# Page09_WIFI_Bluetooth.net
KiCad netlist of a schematic drawn in Altium Designer
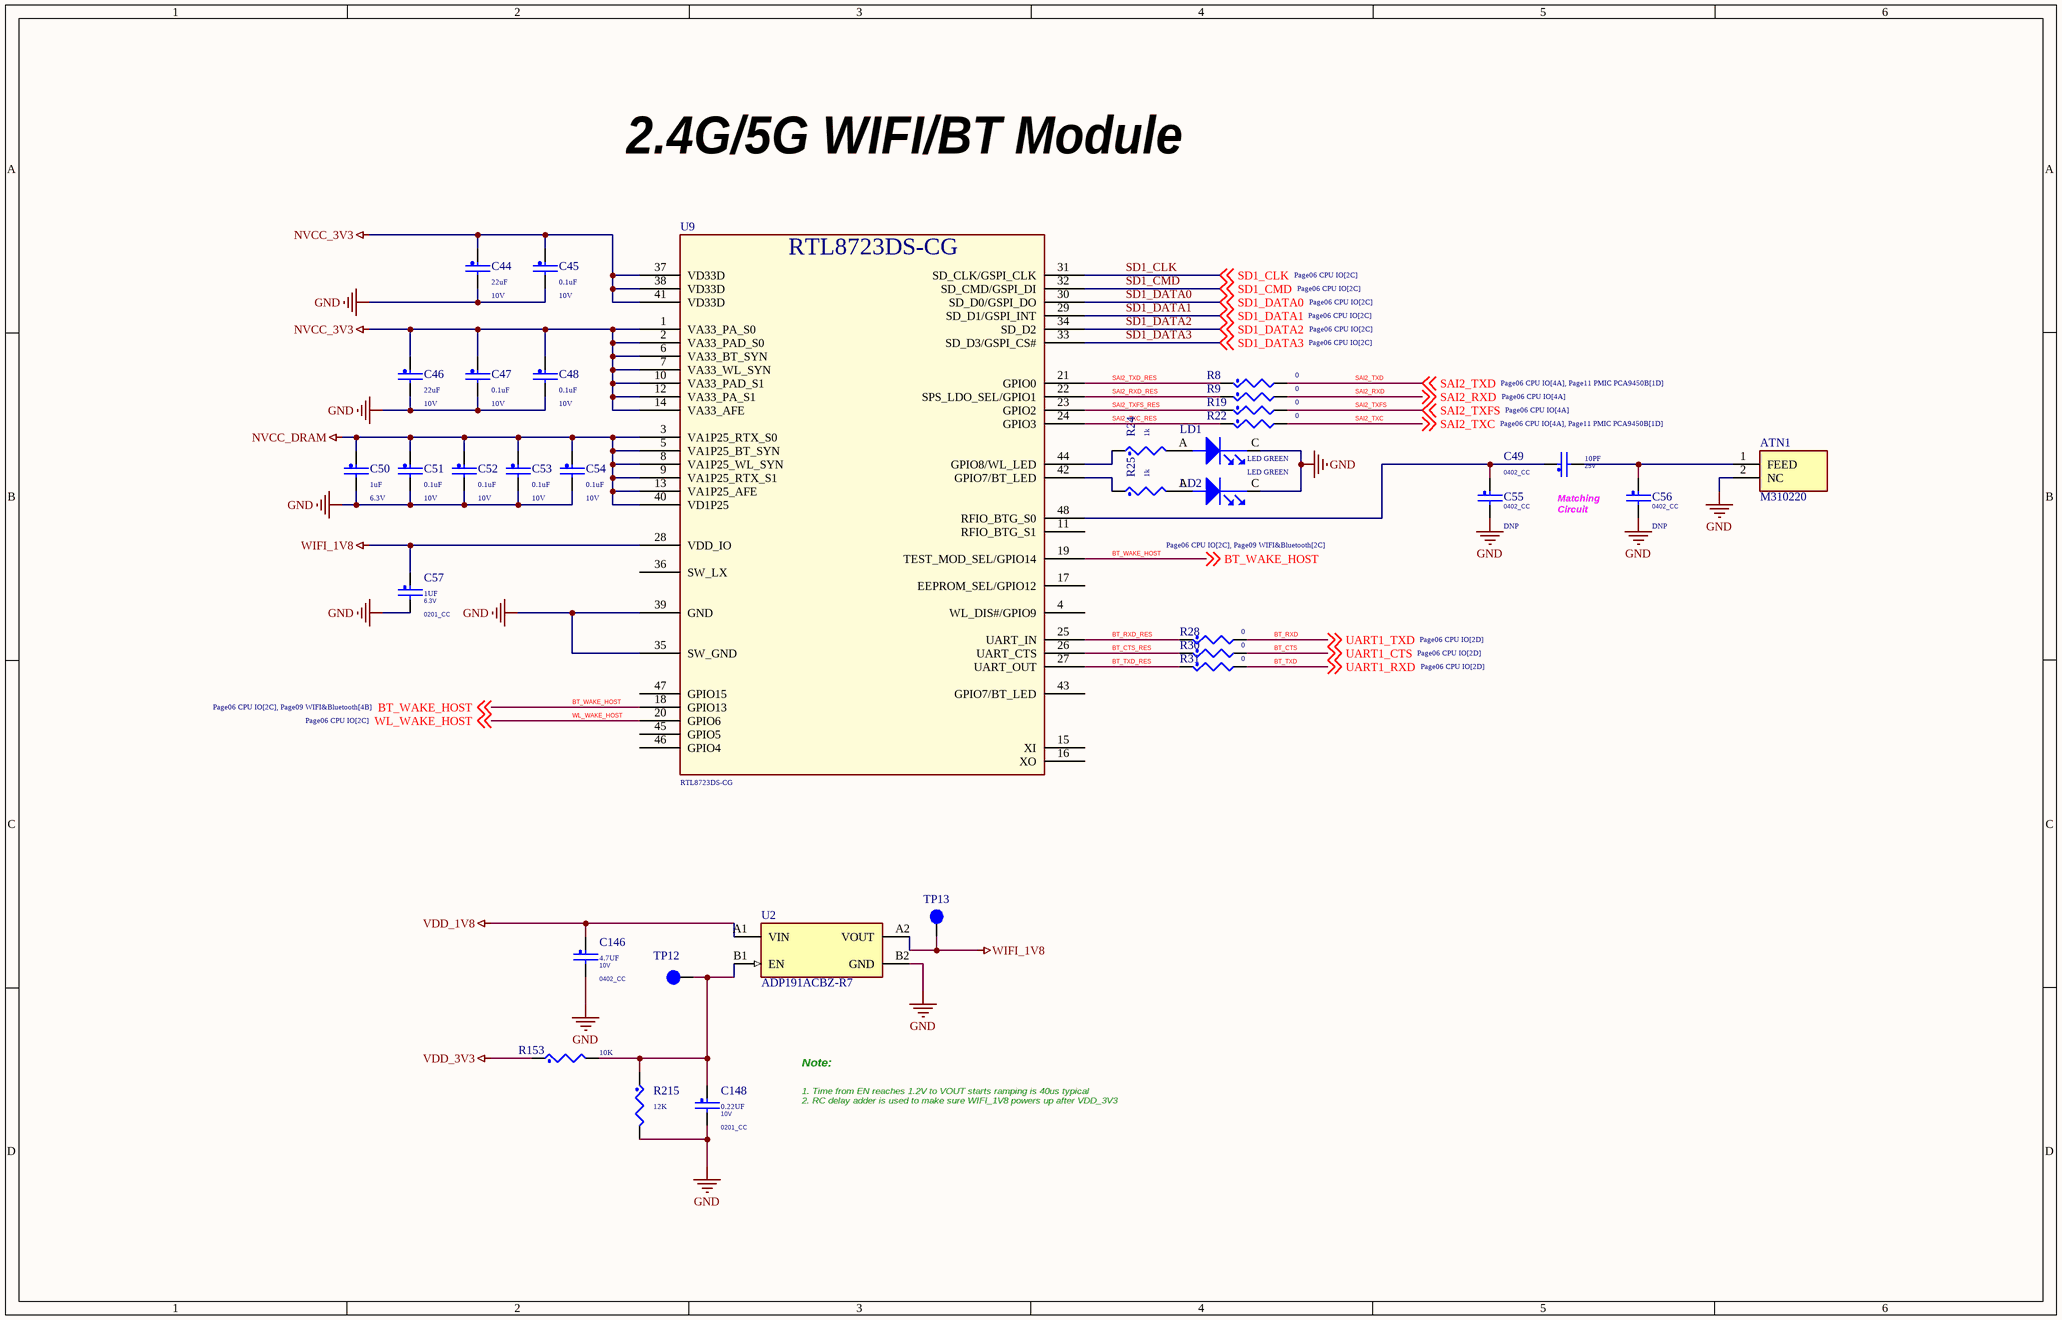
[diagram p0: Page09 WIFI&Bluetooth.SchDoc]

(export (version "E")
  (design (tool "Eeschema 10.0.6"))
  (components
    (comp (ref "ATN1")
      (value "M310220")
      (footprint "M310220")
      (description "Antennas Ceramic Chip ANTENNA BT/WLAN 2.4-2.5GHz")
      (libsource (lib "M310220") (part "M310220"))
    )
    (comp (ref "C44")
      (value "22uF")
      (footprint "0603_CC")
      (fields (field (name "VOLTAGE") "10V"))
      (libsource (lib "AA_iMX8_M_") (part "CAP_NP"))
    )
    (comp (ref "C45")
      (value "0.1uF")
      (footprint "0201_CC - C")
      (fields (field (name "VOLTAGE") "10V"))
      (libsource (lib "AA_iMX8_M_") (part "CAP_NP"))
    )
    (comp (ref "C46")
      (value "22uF")
      (footprint "0603_CC")
      (fields (field (name "VOLTAGE") "10V"))
      (libsource (lib "AA_iMX8_M_") (part "CAP_NP"))
    )
    (comp (ref "C47")
      (value "0.1uF")
      (footprint "0201_CC - C")
      (fields (field (name "VOLTAGE") "10V"))
      (libsource (lib "AA_iMX8_M_") (part "CAP_NP"))
    )
    (comp (ref "C48")
      (value "0.1uF")
      (footprint "0201_CC - C")
      (fields (field (name "VOLTAGE") "10V"))
      (libsource (lib "AA_iMX8_M_") (part "CAP_NP"))
    )
    (comp (ref "C49")
      (value "10PF")
      (footprint "0402_CC - C")
      (description "CAP CER 10PF 25V 5% C0G 0402")
      (fields
        (field (name "VOLTAGE") "25V")
        (field (name "TOLERANCE") "5%")
        (field (name "PCB FOOTPRINT") "0402_CC")
      )
      (libsource (lib "*") (part "CAP_NP"))
    )
    (comp (ref "C50")
      (value "1uF")
      (footprint "0201_CC - C")
      (fields (field (name "VOLTAGE") "6.3V"))
      (libsource (lib "AA_iMX8_M_") (part "CAP_NP"))
    )
    (comp (ref "C51")
      (value "0.1uF")
      (footprint "0201_CC - C")
      (fields (field (name "VOLTAGE") "10V"))
      (libsource (lib "AA_iMX8_M_") (part "CAP_NP"))
    )
    (comp (ref "C52")
      (value "0.1uF")
      (footprint "0201_CC - C")
      (fields (field (name "VOLTAGE") "10V"))
      (libsource (lib "AA_iMX8_M_") (part "CAP_NP"))
    )
    (comp (ref "C53")
      (value "0.1uF")
      (footprint "0201_CC - C")
      (fields (field (name "VOLTAGE") "10V"))
      (libsource (lib "AA_iMX8_M_") (part "CAP_NP"))
    )
    (comp (ref "C54")
      (value "0.1uF")
      (footprint "0201_CC - C")
      (fields (field (name "VOLTAGE") "10V"))
      (libsource (lib "AA_iMX8_M_") (part "CAP_NP"))
    )
    (comp (ref "C55")
      (value "10PF")
      (footprint "0402_CC - C")
      (description "CAP CER 10PF 25V 5% C0G 0402")
      (fields
        (field (name "ASSY_OPT") "DNP")
        (field (name "TOLERANCE") "5%")
        (field (name "VOLTAGE") "25V")
        (field (name "PCB FOOTPRINT") "0402_CC")
      )
      (libsource (lib "*") (part "CAP_NP"))
    )
    (comp (ref "C56")
      (value "10PF")
      (footprint "0402_CC - C")
      (description "CAP CER 10PF 25V 5% C0G 0402")
      (fields
        (field (name "ASSY_OPT") "DNP")
        (field (name "VOLTAGE") "25V")
        (field (name "TOLERANCE") "5%")
        (field (name "PCB FOOTPRINT") "0402_CC")
      )
      (libsource (lib "*") (part "CAP_NP"))
    )
    (comp (ref "C57")
      (value "1UF")
      (footprint "0201_CC - C")
      (description "CAP CER 1uF 6.3V 20% X5R 0201")
      (fields
        (field (name "PCB FOOTPRINT") "0201_CC")
        (field (name "TOLERANCE") "20%")
        (field (name "VOLTAGE") "6.3V")
      )
      (libsource (lib "*") (part "CAP_NP"))
    )
    (comp (ref "C146")
      (value "4.7UF")
      (footprint "0402_CC - C")
      (description "CAP CER 4.7uF 10V 10% X5R 0402")
      (fields
        (field (name "PCB FOOTPRINT") "0402_CC")
        (field (name "TOLERANCE") "10%")
        (field (name "VOLTAGE") "10V")
      )
      (libsource (lib "*") (part "CAP_NP"))
    )
    (comp (ref "C148")
      (value "0.22UF")
      (footprint "0201_CC - C")
      (description "CAP CER 0.22UF 10V 20% X5R 0201")
      (fields
        (field (name "VOLTAGE") "10V")
        (field (name "TOLERANCE") "20%")
        (field (name "PCB FOOTPRINT") "0201_CC")
      )
      (libsource (lib "*") (part "CAP_NP"))
    )
    (comp (ref "LD1")
      (value "LED GREEN")
      (footprint "LED_0603")
      (description "LED GRN SGL 25MA SMT 0603")
      (fields (field (name "VOLTAGE") "2V"))
      (libsource (lib "*") (part "LED"))
    )
    (comp (ref "LD2")
      (value "LED GREEN")
      (footprint "LED_0603")
      (description "LED GRN SGL 25MA SMT 0603")
      (fields (field (name "VOLTAGE") "2V"))
      (libsource (lib "*") (part "LED"))
    )
    (comp (ref "R8")
      (value "0")
      (footprint "0402_CC_RES")
      (description "RES MF ZERO OHM 1/16W 5% 0402")
      (fields (field (name "VOLTAGE") "1/16W") (field (name "TOLERANCE") "5%"))
      (libsource (lib "*") (part "RES"))
    )
    (comp (ref "R9")
      (value "0")
      (footprint "0402_CC_RES")
      (description "RES MF ZERO OHM 1/16W 5% 0402")
      (fields (field (name "VOLTAGE") "1/16W") (field (name "TOLERANCE") "5%"))
      (libsource (lib "*") (part "RES"))
    )
    (comp (ref "R19")
      (value "0")
      (footprint "0402_CC_RES")
      (description "RES MF ZERO OHM 1/16W 5% 0402")
      (fields (field (name "VOLTAGE") "1/16W") (field (name "TOLERANCE") "5%"))
      (libsource (lib "*") (part "RES"))
    )
    (comp (ref "R22")
      (value "0")
      (footprint "0402_CC_RES")
      (description "RES MF ZERO OHM 1/16W 5% 0402")
      (fields (field (name "VOLTAGE") "1/16W") (field (name "TOLERANCE") "5%"))
      (libsource (lib "*") (part "RES"))
    )
    (comp (ref "R24")
      (value "1k")
      (footprint "0201_RES")
      (description "RES MF 1.0K OHM 1/20W 1% 30V -55+155C 0201")
      (fields (field (name "VOLTAGE") "30") (field (name "TOLERANCE") "1%"))
      (libsource (lib "*") (part "RES"))
    )
    (comp (ref "R25")
      (value "1k")
      (footprint "0201_RES")
      (description "RES MF 1.0K OHM 1/20W 1% 30V -55+155C 0201")
      (fields (field (name "VOLTAGE") "30") (field (name "TOLERANCE") "1%"))
      (libsource (lib "*") (part "RES"))
    )
    (comp (ref "R28")
      (value "0")
      (footprint "0402_CC_RES")
      (description "RES MF ZERO OHM 1/16W 5% 0402")
      (fields (field (name "VOLTAGE") "1/16W") (field (name "TOLERANCE") "5%"))
      (libsource (lib "*") (part "RES"))
    )
    (comp (ref "R30")
      (value "0")
      (footprint "0402_CC_RES")
      (description "RES MF ZERO OHM 1/16W 5% 0402")
      (fields (field (name "VOLTAGE") "1/16W") (field (name "TOLERANCE") "5%"))
      (libsource (lib "*") (part "RES"))
    )
    (comp (ref "R31")
      (value "0")
      (footprint "0402_CC_RES")
      (description "RES MF ZERO OHM 1/16W 5% 0402")
      (fields (field (name "VOLTAGE") "1/16W") (field (name "TOLERANCE") "5%"))
      (libsource (lib "*") (part "RES"))
    )
    (comp (ref "R153")
      (value "10K")
      (footprint "0201_RES")
      (description "RES MF 10K 1/20W 5% 0201")
      (fields (field (name "TOLERANCE") "5%"))
      (libsource (lib "*") (part "RES"))
    )
    (comp (ref "R215")
      (value "12K")
      (footprint "0201_RES")
      (description "RES MF 12K 1/20W 1% 0201")
      (fields (field (name "VOLTAGE") "1/20W") (field (name "TOLERANCE") "1%"))
      (libsource (lib "*") (part "RES"))
    )
    (comp (ref "TP12")
      (value "tpad_020")
      (footprint "Test Pin")
      (description "TEST POINT PAD 0.5MM DIA SMT, NO PART TO ORDER")
      (libsource (lib "*") (part "TESTLOOP"))
    )
    (comp (ref "TP13")
      (value "tpad_020")
      (footprint "Test Pin")
      (description "TEST POINT PAD 0.5MM DIA SMT, NO PART TO ORDER")
      (libsource (lib "*") (part "TESTLOOP"))
    )
    (comp (ref "U2")
      (value "ADP191ACBZ-R7")
      (footprint "FP-CB-4-3-MFG")
      (description "IC PWR SWITCH P-CHAN 1:1 4WLCSP")
      (libsource (lib "Altium Content Vault") (part "55c8c918aceb6f1b08494a2ec7cb5d6"))
    )
    (comp (ref "U9")
      (value "RTL8723DS-CG")
      (footprint "RTL8723DS-CG")
      (libsource (lib "Altium starter project NANO") (part "RTL8723DS-CG"))
    )
  )
  (nets
    (net (code "1") (name "/BT_CTS_RES") (class "Default")
      (node (ref "R30") (pin "1") (pinfunction "1_1") (pintype "passive"))
      (node (ref "U9") (pin "26") (pinfunction "UART_CTS_26") (pintype "passive"))
    )
    (net (code "2") (name "/BT_RXD_RES") (class "Default")
      (node (ref "R28") (pin "1") (pinfunction "1_1") (pintype "passive"))
      (node (ref "U9") (pin "25") (pinfunction "UART_IN_25") (pintype "passive"))
    )
    (net (code "3") (name "/BT_TXD_RES") (class "Default")
      (node (ref "R31") (pin "1") (pinfunction "1_1") (pintype "passive"))
      (node (ref "U9") (pin "27") (pinfunction "UART_OUT_27") (pintype "passive"))
    )
    (net (code "4") (name "/SAI2_RXD_RES") (class "Default")
      (node (ref "R9") (pin "1") (pinfunction "1_1") (pintype "passive"))
      (node (ref "U9") (pin "22") (pinfunction "SPS_LDO_SEL/GPIO1_22") (pintype "passive"))
    )
    (net (code "5") (name "/SAI2_TXC_RES") (class "Default")
      (node (ref "R22") (pin "1") (pinfunction "1_1") (pintype "passive"))
      (node (ref "U9") (pin "24") (pinfunction "GPIO3_24") (pintype "passive"))
    )
    (net (code "6") (name "/SAI2_TXD_RES") (class "Default")
      (node (ref "R8") (pin "1") (pinfunction "1_1") (pintype "passive"))
      (node (ref "U9") (pin "21") (pinfunction "GPIO0_21") (pintype "passive"))
    )
    (net (code "7") (name "/SAI2_TXFS_RES") (class "Default")
      (node (ref "R19") (pin "1") (pinfunction "1_1") (pintype "passive"))
      (node (ref "U9") (pin "23") (pinfunction "GPIO2_23") (pintype "passive"))
    )
    (net (code "8") (name "BT_WAKE_HOST") (class "Default")
      (node (ref "U9") (pin "18") (pinfunction "GPIO13_18") (pintype "passive"))
      (node (ref "U9") (pin "19") (pinfunction "TEST_MOD_SEL/GPIO14_19") (pintype "passive"))
    )
    (net (code "9") (name "GND") (class "Default")
      (node (ref "ATN1") (pin "2") (pinfunction "NC_2") (pintype "passive"))
      (node (ref "C146") (pin "2") (pinfunction "2_2") (pintype "passive"))
      (node (ref "C148") (pin "2") (pinfunction "2_2") (pintype "passive"))
      (node (ref "C44") (pin "2") (pinfunction "2_2") (pintype "passive"))
      (node (ref "C45") (pin "2") (pinfunction "2_2") (pintype "passive"))
      (node (ref "C46") (pin "2") (pinfunction "2_2") (pintype "passive"))
      (node (ref "C47") (pin "2") (pinfunction "2_2") (pintype "passive"))
      (node (ref "C48") (pin "2") (pinfunction "2_2") (pintype "passive"))
      (node (ref "C50") (pin "2") (pinfunction "2_2") (pintype "passive"))
      (node (ref "C51") (pin "2") (pinfunction "2_2") (pintype "passive"))
      (node (ref "C52") (pin "2") (pinfunction "2_2") (pintype "passive"))
      (node (ref "C53") (pin "2") (pinfunction "2_2") (pintype "passive"))
      (node (ref "C54") (pin "2") (pinfunction "2_2") (pintype "passive"))
      (node (ref "C55") (pin "2") (pinfunction "2_2") (pintype "passive"))
      (node (ref "C56") (pin "2") (pinfunction "2_2") (pintype "passive"))
      (node (ref "C57") (pin "2") (pinfunction "2_2") (pintype "passive"))
      (node (ref "LD1") (pin "C") (pinfunction "CATHODE_C") (pintype "passive"))
      (node (ref "LD2") (pin "C") (pinfunction "CATHODE_C") (pintype "passive"))
      (node (ref "R215") (pin "2") (pinfunction "2_2") (pintype "passive"))
      (node (ref "U2") (pin "B2") (pinfunction "GND_B2") (pintype "power_in"))
      (node (ref "U9") (pin "35") (pinfunction "SW_GND_35") (pintype "passive"))
      (node (ref "U9") (pin "39") (pinfunction "GND_39") (pintype "passive"))
    )
    (net (code "10") (name "NVCC_3V3") (class "Default")
      (node (ref "C44") (pin "1") (pinfunction "1_1") (pintype "passive"))
      (node (ref "C45") (pin "1") (pinfunction "1_1") (pintype "passive"))
      (node (ref "C46") (pin "1") (pinfunction "1_1") (pintype "passive"))
      (node (ref "C47") (pin "1") (pinfunction "1_1") (pintype "passive"))
      (node (ref "C48") (pin "1") (pinfunction "1_1") (pintype "passive"))
      (node (ref "U9") (pin "1") (pinfunction "VA33_PA_S0_1") (pintype "passive"))
      (node (ref "U9") (pin "10") (pinfunction "VA33_PAD_S1_10") (pintype "passive"))
      (node (ref "U9") (pin "12") (pinfunction "VA33_PA_S1_12") (pintype "passive"))
      (node (ref "U9") (pin "14") (pinfunction "VA33_AFE_14") (pintype "passive"))
      (node (ref "U9") (pin "2") (pinfunction "VA33_PAD_S0_2") (pintype "passive"))
      (node (ref "U9") (pin "37") (pinfunction "VD33D_37") (pintype "passive"))
      (node (ref "U9") (pin "38") (pinfunction "VD33D_38") (pintype "passive"))
      (node (ref "U9") (pin "41") (pinfunction "VD33D_41") (pintype "passive"))
      (node (ref "U9") (pin "6") (pinfunction "VA33_BT_SYN_6") (pintype "passive"))
      (node (ref "U9") (pin "7") (pinfunction "VA33_WL_SYN_7") (pintype "passive"))
    )
    (net (code "11") (name "NVCC_DRAM") (class "Default")
      (node (ref "C50") (pin "1") (pinfunction "1_1") (pintype "passive"))
      (node (ref "C51") (pin "1") (pinfunction "1_1") (pintype "passive"))
      (node (ref "C52") (pin "1") (pinfunction "1_1") (pintype "passive"))
      (node (ref "C53") (pin "1") (pinfunction "1_1") (pintype "passive"))
      (node (ref "C54") (pin "1") (pinfunction "1_1") (pintype "passive"))
      (node (ref "U9") (pin "13") (pinfunction "VA1P25_AFE_13") (pintype "passive"))
      (node (ref "U9") (pin "3") (pinfunction "VA1P25_RTX_S0_3") (pintype "passive"))
      (node (ref "U9") (pin "40") (pinfunction "VD1P25_40") (pintype "passive"))
      (node (ref "U9") (pin "5") (pinfunction "VA1P25_BT_SYN_5") (pintype "passive"))
      (node (ref "U9") (pin "8") (pinfunction "VA1P25_WL_SYN_8") (pintype "passive"))
      (node (ref "U9") (pin "9") (pinfunction "VA1P25_RTX_S1_9") (pintype "passive"))
    )
    (net (code "12") (name "Net-(ATN1-FEED)") (class "Default")
      (node (ref "ATN1") (pin "1") (pinfunction "FEED_1") (pintype "passive"))
      (node (ref "C49") (pin "2") (pinfunction "2_2") (pintype "passive"))
      (node (ref "C56") (pin "1") (pinfunction "1_1") (pintype "passive"))
    )
    (net (code "13") (name "Net-(LD1-ANODE)") (class "Default")
      (node (ref "LD1") (pin "A") (pinfunction "ANODE_A") (pintype "passive"))
      (node (ref "R24") (pin "2") (pinfunction "2_2") (pintype "passive"))
    )
    (net (code "14") (name "Net-(LD2-ANODE)") (class "Default")
      (node (ref "LD2") (pin "A") (pinfunction "ANODE_A") (pintype "passive"))
      (node (ref "R25") (pin "2") (pinfunction "2_2") (pintype "passive"))
    )
    (net (code "15") (name "Net-(R25-Pad1)") (class "Default")
      (node (ref "R25") (pin "1") (pinfunction "1_1") (pintype "passive"))
      (node (ref "U9") (pin "42") (pinfunction "GPIO7/BT_LED_42") (pintype "passive"))
    )
    (net (code "16") (name "Net-(TP12-Pin1)") (class "Default")
      (node (ref "C148") (pin "1") (pinfunction "1_1") (pintype "passive"))
      (node (ref "R153") (pin "2") (pinfunction "2_2") (pintype "passive"))
      (node (ref "R215") (pin "1") (pinfunction "1_1") (pintype "passive"))
      (node (ref "TP12") (pin "1") (pinfunction "Pin1_1") (pintype "passive"))
      (node (ref "U2") (pin "B1") (pinfunction "EN_B1") (pintype "input"))
    )
    (net (code "17") (name "Net-(U9-GPIO8{slash}WL_LED)") (class "Default")
      (node (ref "R24") (pin "1") (pinfunction "1_1") (pintype "passive"))
      (node (ref "U9") (pin "44") (pinfunction "GPIO8/WL_LED_44") (pintype "passive"))
    )
    (net (code "18") (name "Net-(U9-RFIO_BTG_S0)") (class "Default")
      (node (ref "C49") (pin "1") (pinfunction "1_1") (pintype "passive"))
      (node (ref "C55") (pin "1") (pinfunction "1_1") (pintype "passive"))
      (node (ref "U9") (pin "48") (pinfunction "RFIO_BTG_S0_48") (pintype "passive"))
    )
    (net (code "19") (name "SAI2_RXD") (class "Default")
      (node (ref "R9") (pin "2") (pinfunction "2_2") (pintype "passive"))
    )
    (net (code "20") (name "SAI2_TXC") (class "Default")
      (node (ref "R22") (pin "2") (pinfunction "2_2") (pintype "passive"))
    )
    (net (code "21") (name "SAI2_TXD") (class "Default")
      (node (ref "R8") (pin "2") (pinfunction "2_2") (pintype "passive"))
    )
    (net (code "22") (name "SAI2_TXFS") (class "Default")
      (node (ref "R19") (pin "2") (pinfunction "2_2") (pintype "passive"))
    )
    (net (code "23") (name "SD1_CLK") (class "Default")
      (node (ref "U9") (pin "31") (pinfunction "SD_CLK/GSPI_CLK_31") (pintype "passive"))
    )
    (net (code "24") (name "SD1_CMD") (class "Default")
      (node (ref "U9") (pin "32") (pinfunction "SD_CMD/GSPI_DI_32") (pintype "passive"))
    )
    (net (code "25") (name "SD1_DATA0") (class "Default")
      (node (ref "U9") (pin "30") (pinfunction "SD_D0/GSPI_DO_30") (pintype "passive"))
    )
    (net (code "26") (name "SD1_DATA1") (class "Default")
      (node (ref "U9") (pin "29") (pinfunction "SD_D1/GSPI_INT_29") (pintype "passive"))
    )
    (net (code "27") (name "SD1_DATA2") (class "Default")
      (node (ref "U9") (pin "34") (pinfunction "SD_D2_34") (pintype "passive"))
    )
    (net (code "28") (name "SD1_DATA3") (class "Default")
      (node (ref "U9") (pin "33") (pinfunction "SD_D3/GSPI_CS#_33") (pintype "passive"))
    )
    (net (code "29") (name "UART1_CTS") (class "Default")
      (node (ref "R30") (pin "2") (pinfunction "2_2") (pintype "passive"))
    )
    (net (code "30") (name "UART1_RXD") (class "Default")
      (node (ref "R31") (pin "2") (pinfunction "2_2") (pintype "passive"))
    )
    (net (code "31") (name "UART1_TXD") (class "Default")
      (node (ref "R28") (pin "2") (pinfunction "2_2") (pintype "passive"))
    )
    (net (code "32") (name "VDD_1V8") (class "Default")
      (node (ref "C146") (pin "1") (pinfunction "1_1") (pintype "passive"))
      (node (ref "U2") (pin "A1") (pinfunction "VIN_A1") (pintype "power_in"))
    )
    (net (code "33") (name "VDD_3V3") (class "Default")
      (node (ref "R153") (pin "1") (pinfunction "1_1") (pintype "passive"))
    )
    (net (code "34") (name "WIFI_1V8") (class "Default")
      (node (ref "C57") (pin "1") (pinfunction "1_1") (pintype "passive"))
      (node (ref "TP13") (pin "1") (pinfunction "Pin1_1") (pintype "passive"))
      (node (ref "U2") (pin "A2") (pinfunction "VOUT_A2") (pintype "power_in"))
      (node (ref "U9") (pin "28") (pinfunction "VDD_IO_28") (pintype "passive"))
    )
    (net (code "35") (name "WL_WAKE_HOST") (class "Default")
      (node (ref "U9") (pin "20") (pinfunction "GPIO6_20") (pintype "passive"))
    )
    (net (code "36") (name "unconnected-(U9-EEPROM_SEL{slash}GPIO12-Pad17)") (class "Default")
      (node (ref "U9") (pin "17") (pinfunction "EEPROM_SEL/GPIO12_17") (pintype "passive"))
    )
    (net (code "37") (name "unconnected-(U9-GPIO4-Pad46)") (class "Default")
      (node (ref "U9") (pin "46") (pinfunction "GPIO4_46") (pintype "passive"))
    )
    (net (code "38") (name "unconnected-(U9-GPIO5-Pad45)") (class "Default")
      (node (ref "U9") (pin "45") (pinfunction "GPIO5_45") (pintype "passive"))
    )
    (net (code "39") (name "unconnected-(U9-GPIO7{slash}BT_LED-Pad43)") (class "Default")
      (node (ref "U9") (pin "43") (pinfunction "GPIO7/BT_LED_43") (pintype "passive"))
    )
    (net (code "40") (name "unconnected-(U9-GPIO15-Pad47)") (class "Default")
      (node (ref "U9") (pin "47") (pinfunction "GPIO15_47") (pintype "passive"))
    )
    (net (code "41") (name "unconnected-(U9-RFIO_BTG_S1-Pad11)") (class "Default")
      (node (ref "U9") (pin "11") (pinfunction "RFIO_BTG_S1_11") (pintype "passive"))
    )
    (net (code "42") (name "unconnected-(U9-SW_LX-Pad36)") (class "Default")
      (node (ref "U9") (pin "36") (pinfunction "SW_LX_36") (pintype "passive"))
    )
    (net (code "43") (name "unconnected-(U9-WL_DIS#{slash}GPIO9-Pad4)") (class "Default")
      (node (ref "U9") (pin "4") (pinfunction "WL_DIS#/GPIO9_4") (pintype "passive"))
    )
    (net (code "44") (name "unconnected-(U9-XI-Pad15)") (class "Default")
      (node (ref "U9") (pin "15") (pinfunction "XI_15") (pintype "passive"))
    )
    (net (code "45") (name "unconnected-(U9-XO-Pad16)") (class "Default")
      (node (ref "U9") (pin "16") (pinfunction "XO_16") (pintype "passive"))
    )
  )
)
